# Main_board.net
KiCad netlist of a schematic drawn in Altium Designer
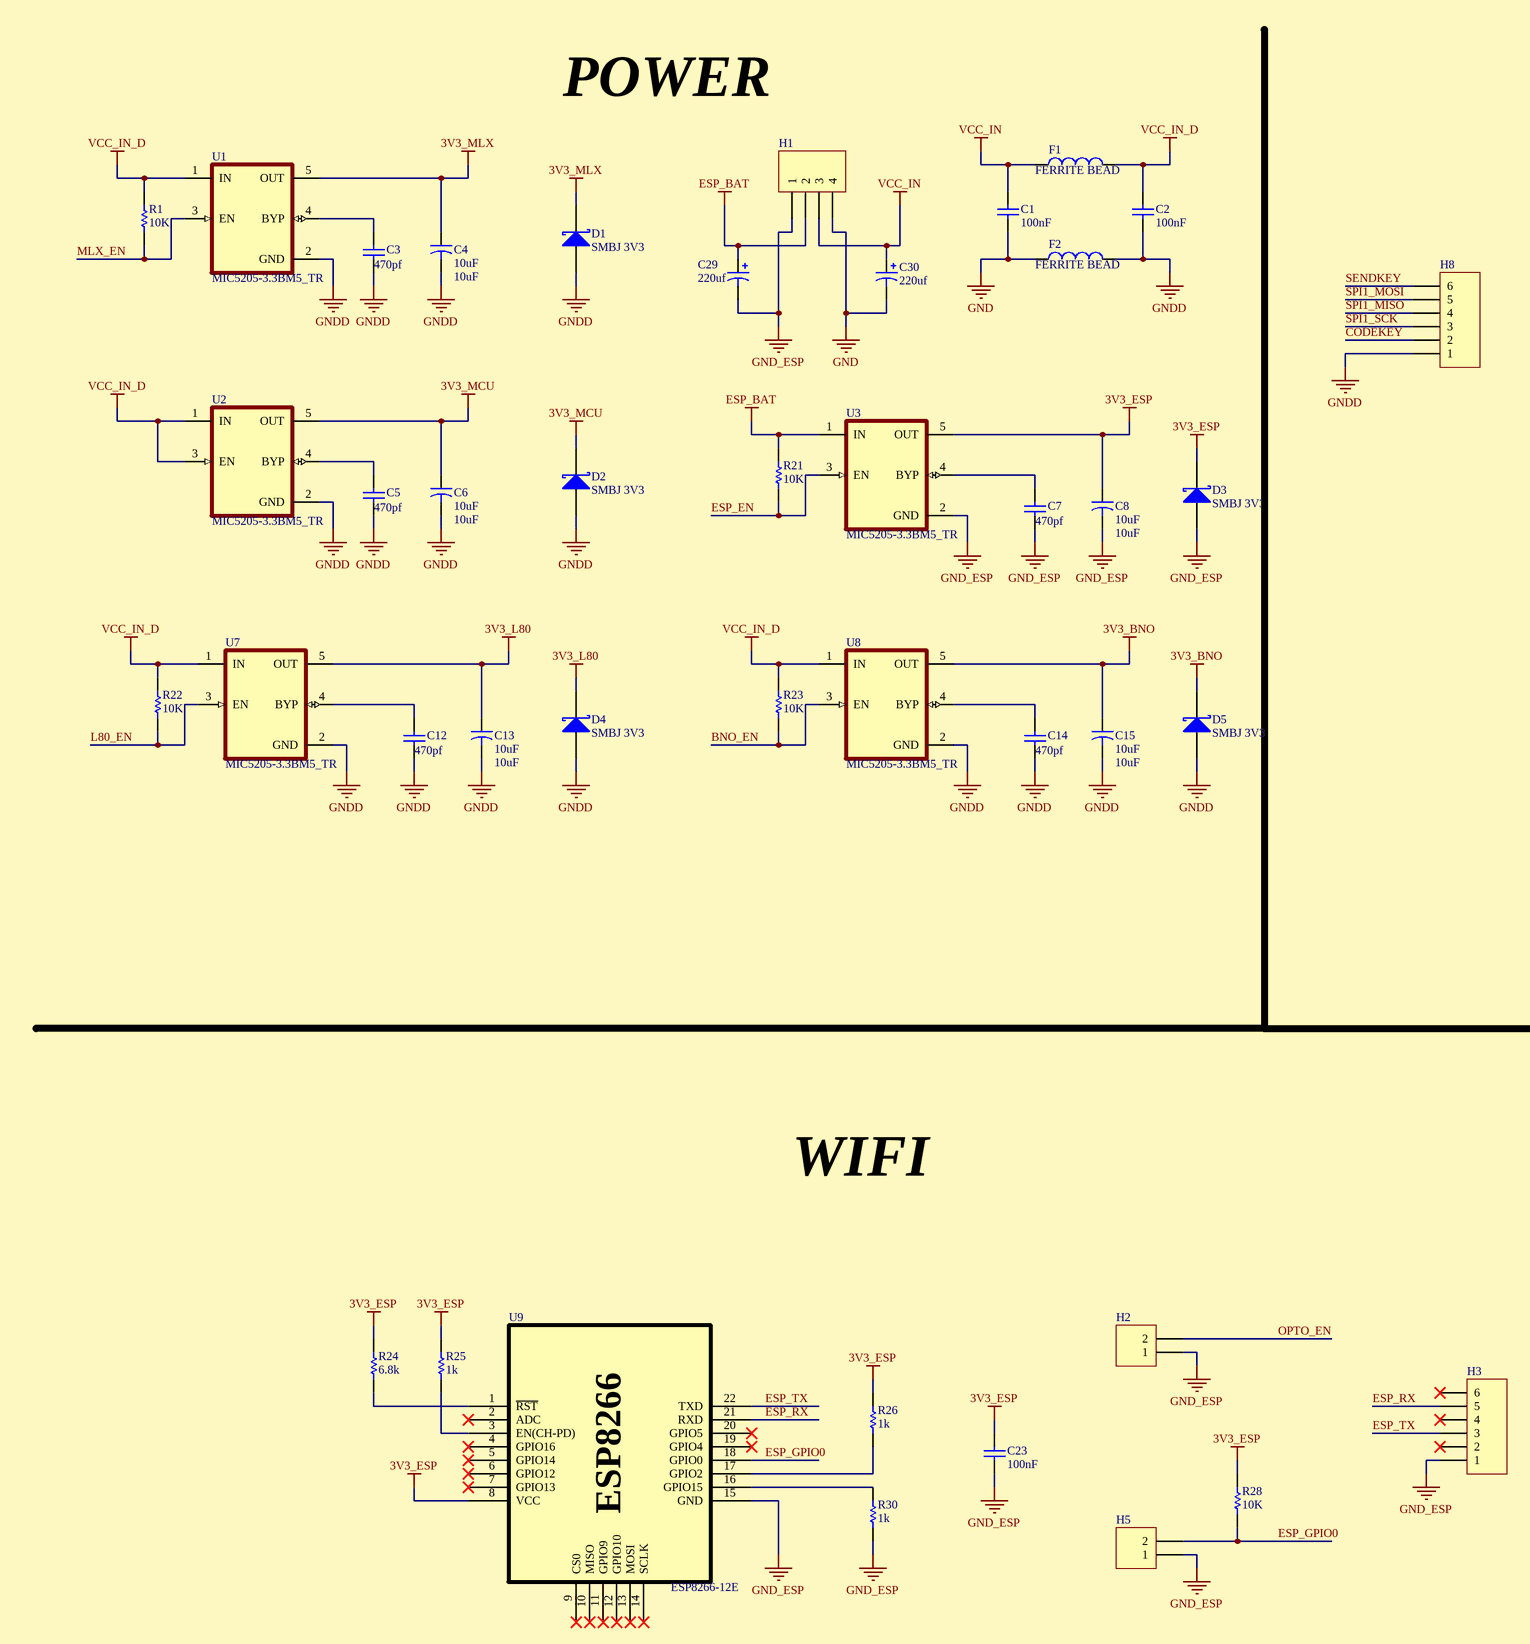
[diagram p0: Main_board.SchDoc, top left]
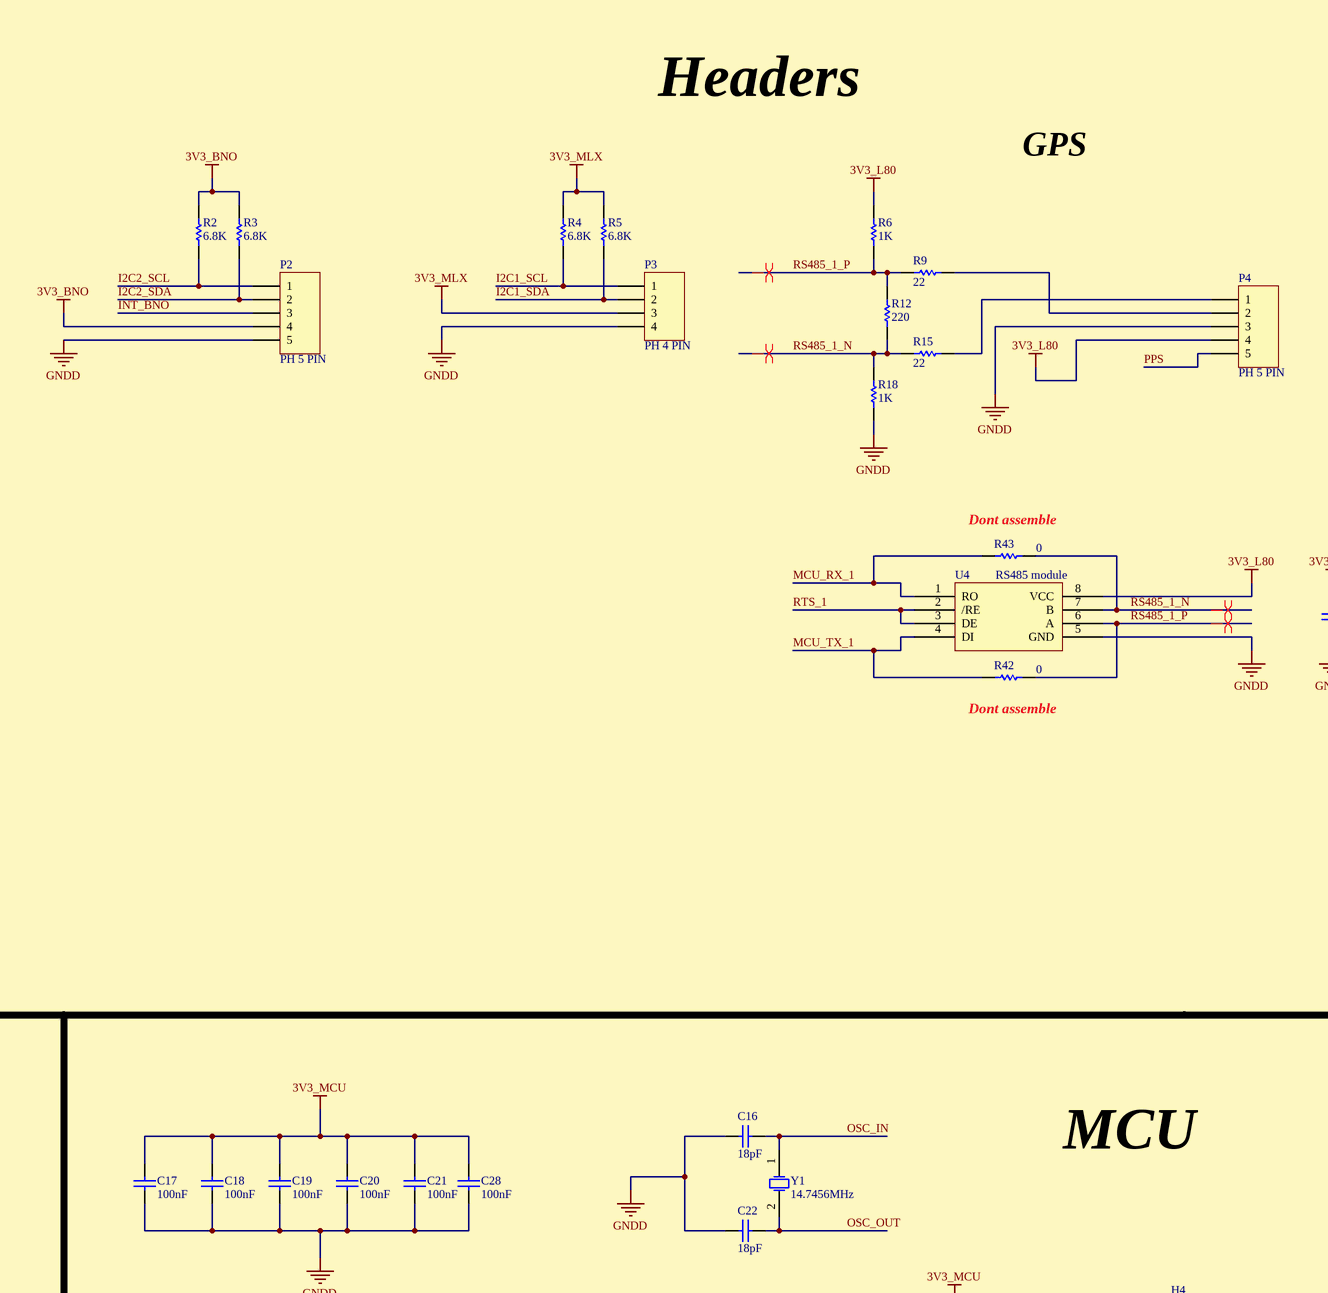
[diagram p1: Main_board.SchDoc, top middle]
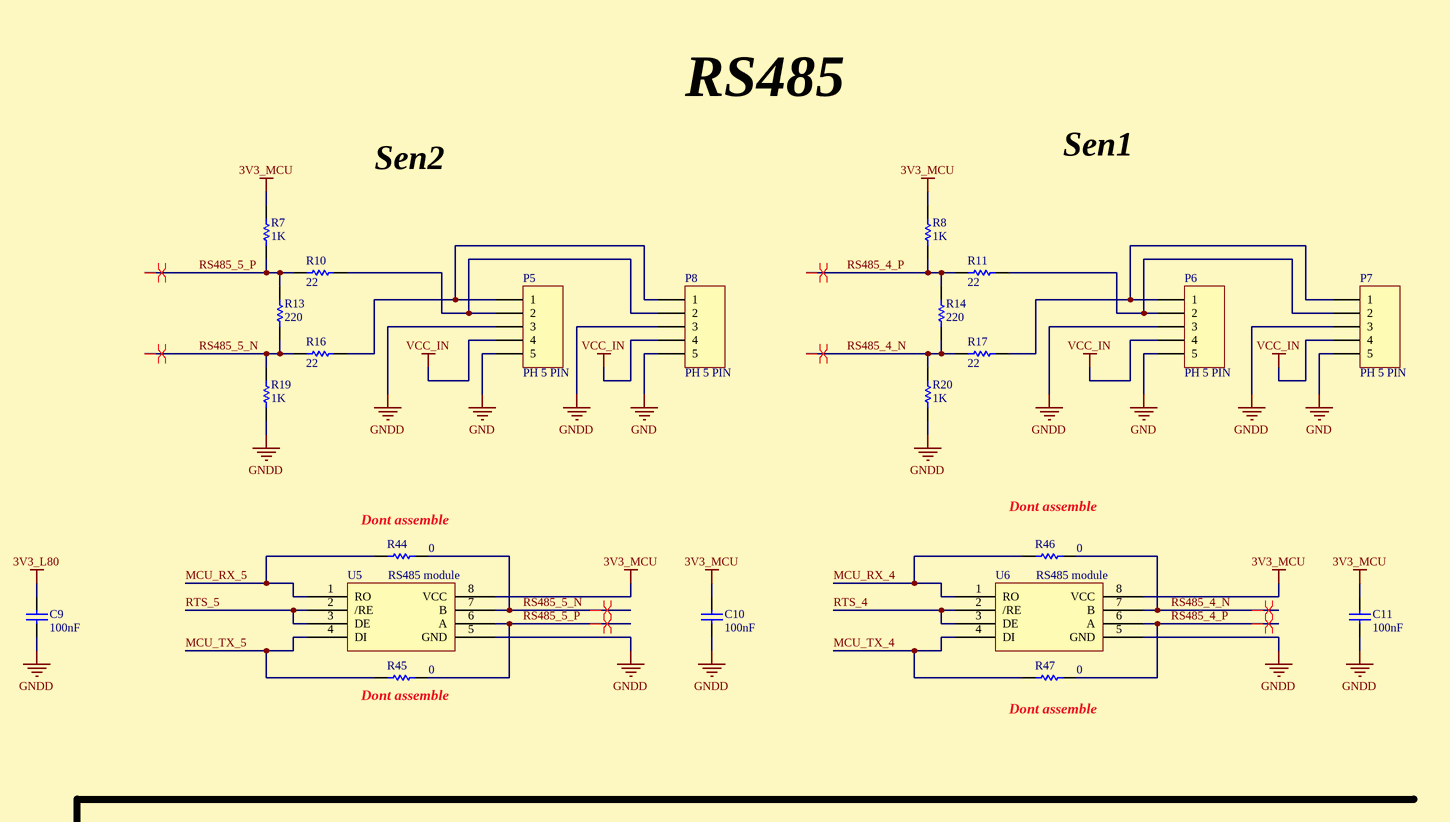
[diagram p2: Main_board.SchDoc, top right]
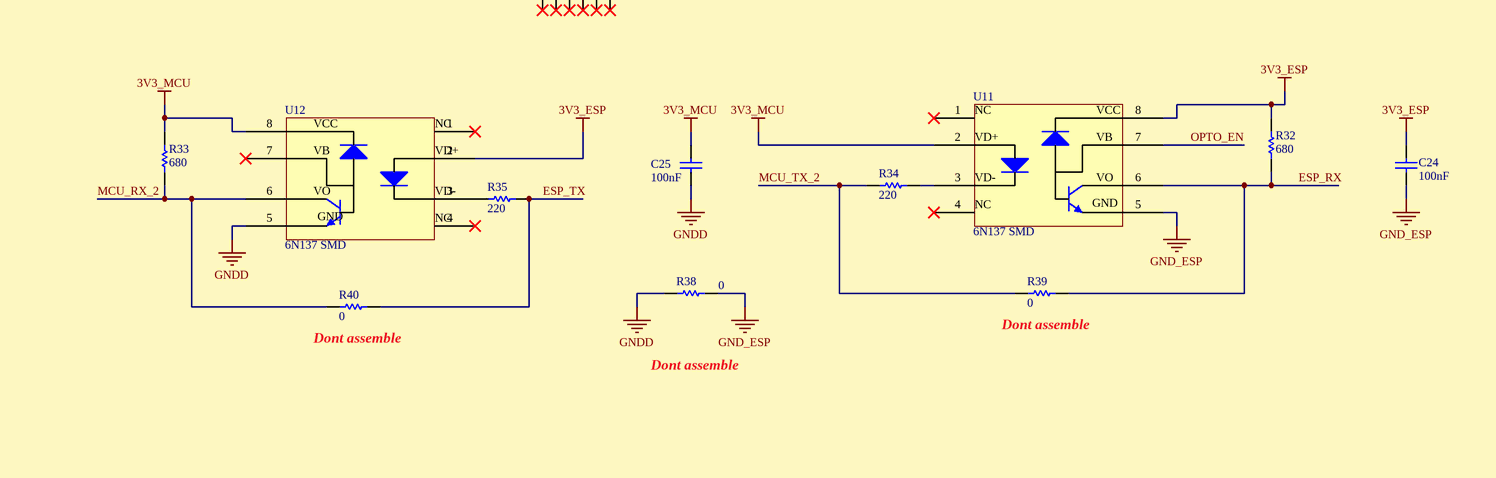
[diagram p3: Main_board.SchDoc, bottom left]
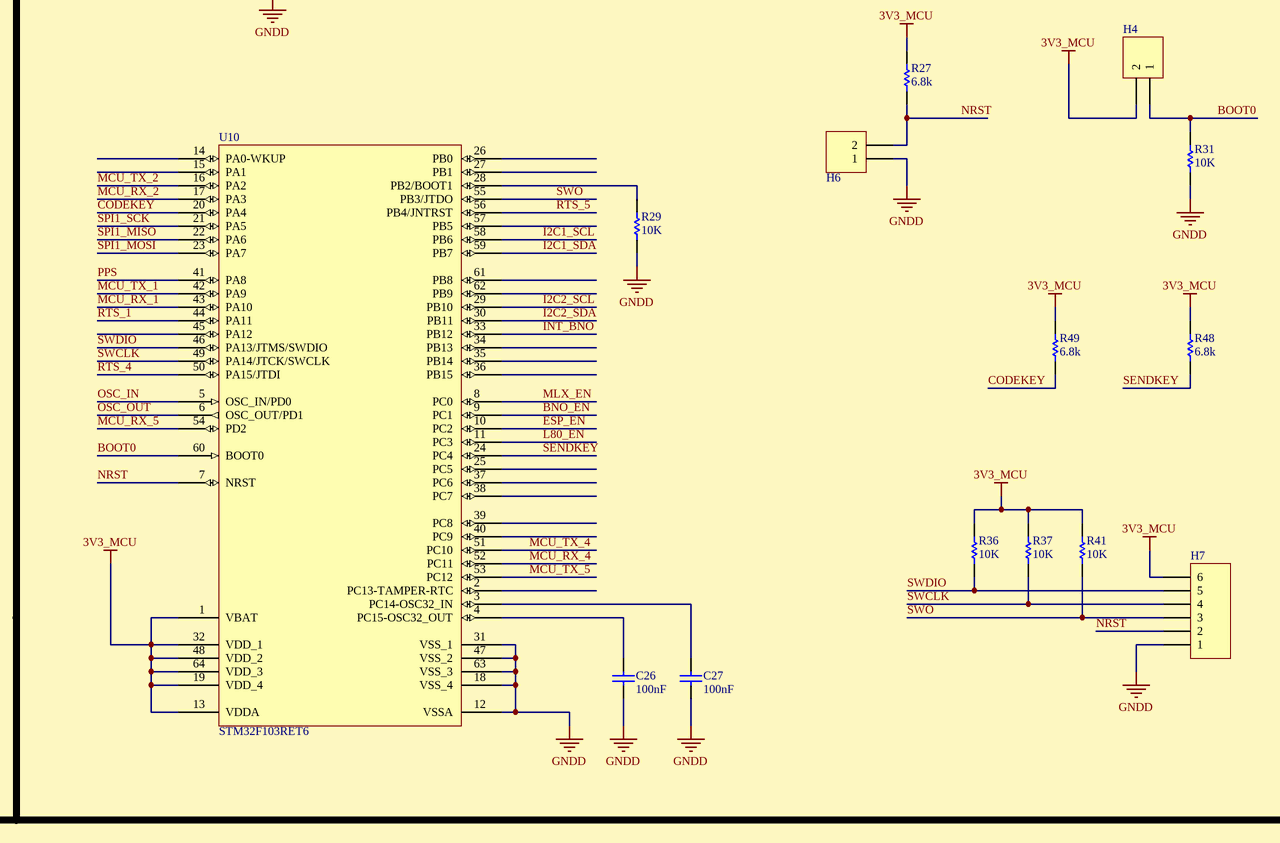
[diagram p4: Main_board.SchDoc, bottom middle]
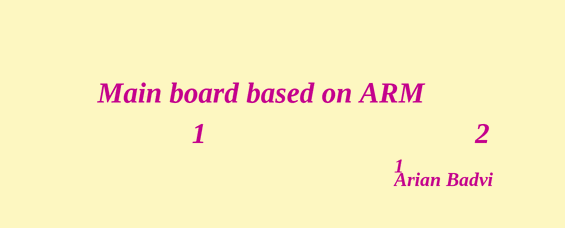
[diagram p5: Main_board.SchDoc, bottom right]

(export (version "E")
  (design (tool "Eeschema 10.0.6"))
  (components
    (comp (ref "C1")
      (value "100nF")
      (footprint "C0805")
      (description "Capacitor")
      (fields (field (name "PUBLISHER") "Altium Limited"))
      (libsource (lib "Miscellaneous Devices") (part "Cap"))
    )
    (comp (ref "C2")
      (value "100nF")
      (footprint "C0805")
      (description "Capacitor")
      (fields (field (name "PUBLISHER") "Altium Limited"))
      (libsource (lib "Miscellaneous Devices") (part "Cap"))
    )
    (comp (ref "C3")
      (value "470pf")
      (footprint "C0805")
      (description "Capacitor, 1206")
      (fields (field (name "PUBLISHER") "Altium Limited"))
      (libsource (lib "Library") (part "Cap"))
    )
    (comp (ref "C4")
      (value "10uF")
      (footprint "CAP_SMD_A")
      (description "Capacitor, 10uf")
      (fields (field (name "ALTIUM_VALUE") "10uF") (field (name "PUBLISHER") "Altium Limited"))
      (libsource (lib "Miscellaneous Devices") (part "Cap2"))
    )
    (comp (ref "C5")
      (value "470pf")
      (footprint "C0805")
      (description "Capacitor, 1206")
      (fields (field (name "PUBLISHER") "Altium Limited"))
      (libsource (lib "Library") (part "Cap"))
    )
    (comp (ref "C6")
      (value "10uF")
      (footprint "CAP_SMD_A")
      (description "Capacitor, 10uf")
      (fields (field (name "ALTIUM_VALUE") "10uF") (field (name "PUBLISHER") "Altium Limited"))
      (libsource (lib "Miscellaneous Devices") (part "Cap2"))
    )
    (comp (ref "C7")
      (value "470pf")
      (footprint "C0805")
      (description "Capacitor, 1206")
      (fields (field (name "PUBLISHER") "Altium Limited"))
      (libsource (lib "Library") (part "Cap"))
    )
    (comp (ref "C8")
      (value "10uF")
      (footprint "CAP_SMD_A")
      (description "Capacitor, 10uf")
      (fields (field (name "ALTIUM_VALUE") "10uF") (field (name "PUBLISHER") "Altium Limited"))
      (libsource (lib "Miscellaneous Devices") (part "Cap2"))
    )
    (comp (ref "C9")
      (value "100nF")
      (footprint "C0805")
      (description "Capacitor")
      (fields (field (name "PUBLISHER") "Altium Limited"))
      (libsource (lib "Miscellaneous Devices") (part "Cap"))
    )
    (comp (ref "C10")
      (value "100nF")
      (footprint "C0805")
      (description "Capacitor")
      (fields (field (name "PUBLISHER") "Altium Limited"))
      (libsource (lib "Miscellaneous Devices") (part "Cap"))
    )
    (comp (ref "C11")
      (value "100nF")
      (footprint "C0805")
      (description "Capacitor")
      (fields (field (name "PUBLISHER") "Altium Limited"))
      (libsource (lib "Miscellaneous Devices") (part "Cap"))
    )
    (comp (ref "C12")
      (value "470pf")
      (footprint "C0805")
      (description "Capacitor, 1206")
      (fields (field (name "PUBLISHER") "Altium Limited"))
      (libsource (lib "Library") (part "Cap"))
    )
    (comp (ref "C13")
      (value "10uF")
      (footprint "CAP_SMD_A")
      (description "Capacitor, 10uf")
      (fields (field (name "ALTIUM_VALUE") "10uF") (field (name "PUBLISHER") "Altium Limited"))
      (libsource (lib "Miscellaneous Devices") (part "Cap2"))
    )
    (comp (ref "C14")
      (value "470pf")
      (footprint "C0805")
      (description "Capacitor, 1206")
      (fields (field (name "PUBLISHER") "Altium Limited"))
      (libsource (lib "Library") (part "Cap"))
    )
    (comp (ref "C15")
      (value "10uF")
      (footprint "CAP_SMD_A")
      (description "Capacitor, 10uf")
      (fields (field (name "ALTIUM_VALUE") "10uF") (field (name "PUBLISHER") "Altium Limited"))
      (libsource (lib "Miscellaneous Devices") (part "Cap2"))
    )
    (comp (ref "C16")
      (value "18pF")
      (footprint "C0805")
      (description "Capacitor")
      (fields (field (name "PUBLISHER") "Altium Limited"))
      (libsource (lib "Miscellaneous Devices") (part "Cap"))
    )
    (comp (ref "C17")
      (value "100nF")
      (footprint "C0805")
      (description "Capacitor")
      (fields (field (name "PUBLISHER") "Altium Limited"))
      (libsource (lib "Miscellaneous Devices") (part "Cap"))
    )
    (comp (ref "C18")
      (value "100nF")
      (footprint "C0805")
      (description "Capacitor")
      (fields (field (name "PUBLISHER") "Altium Limited"))
      (libsource (lib "Miscellaneous Devices") (part "Cap"))
    )
    (comp (ref "C19")
      (value "100nF")
      (footprint "C0805")
      (description "Capacitor")
      (fields (field (name "PUBLISHER") "Altium Limited"))
      (libsource (lib "Miscellaneous Devices") (part "Cap"))
    )
    (comp (ref "C20")
      (value "100nF")
      (footprint "C0805")
      (description "Capacitor")
      (fields (field (name "PUBLISHER") "Altium Limited"))
      (libsource (lib "Miscellaneous Devices") (part "Cap"))
    )
    (comp (ref "C21")
      (value "100nF")
      (footprint "C0805")
      (description "Capacitor")
      (fields (field (name "PUBLISHER") "Altium Limited"))
      (libsource (lib "Miscellaneous Devices") (part "Cap"))
    )
    (comp (ref "C22")
      (value "18pF")
      (footprint "C0805")
      (description "Capacitor")
      (fields (field (name "PUBLISHER") "Altium Limited"))
      (libsource (lib "Miscellaneous Devices") (part "Cap"))
    )
    (comp (ref "C23")
      (value "100nF")
      (footprint "C0805")
      (description "Capacitor")
      (fields (field (name "PUBLISHER") "Altium Limited"))
      (libsource (lib "Miscellaneous Devices") (part "Cap"))
    )
    (comp (ref "C24")
      (value "100nF")
      (footprint "C0805")
      (description "Capacitor")
      (fields (field (name "PUBLISHER") "Altium Limited"))
      (libsource (lib "Miscellaneous Devices") (part "Cap"))
    )
    (comp (ref "C25")
      (value "100nF")
      (footprint "C0805")
      (description "Capacitor, 1206")
      (fields (field (name "PUBLISHER") "Altium Limited"))
      (libsource (lib "Miscellaneous Devices") (part "Cap"))
    )
    (comp (ref "C26")
      (value "100nF")
      (footprint "C0805")
      (description "Capacitor")
      (fields (field (name "PUBLISHER") "Altium Limited"))
      (libsource (lib "Miscellaneous Devices") (part "Cap"))
    )
    (comp (ref "C27")
      (value "100nF")
      (footprint "C0805")
      (description "Capacitor")
      (fields (field (name "PUBLISHER") "Altium Limited"))
      (libsource (lib "Miscellaneous Devices") (part "Cap"))
    )
    (comp (ref "C28")
      (value "100nF")
      (footprint "C0805")
      (description "Capacitor")
      (fields (field (name "PUBLISHER") "Altium Limited"))
      (libsource (lib "Miscellaneous Devices") (part "Cap"))
    )
    (comp (ref "C29")
      (value "220uf")
      (footprint "C_CYL_SMD2")
      (description "pol cap, Ele")
      (fields (field (name "PUBLISHER") "Altium Limited"))
      (libsource (lib "Library") (part "Cap Pol"))
    )
    (comp (ref "C30")
      (value "220uf")
      (footprint "C_CYL_SMD2")
      (description "pol cap, Ele")
      (fields (field (name "PUBLISHER") "Altium Limited"))
      (libsource (lib "Library") (part "Cap Pol"))
    )
    (comp (ref "D1")
      (value "SMBJ 3V3")
      (footprint "TVS")
      (description "TVS")
      (fields (field (name "PUBLISHER") "Altium Limited"))
      (libsource (lib "Miscellaneous Devices") (part "Diode 18TQ045"))
    )
    (comp (ref "D2")
      (value "SMBJ 3V3")
      (footprint "TVS")
      (description "TVS")
      (fields (field (name "PUBLISHER") "Altium Limited"))
      (libsource (lib "Miscellaneous Devices") (part "Diode 18TQ045"))
    )
    (comp (ref "D3")
      (value "SMBJ 3V3")
      (footprint "TVS")
      (description "TVS")
      (fields (field (name "PUBLISHER") "Altium Limited"))
      (libsource (lib "Miscellaneous Devices") (part "Diode 18TQ045"))
    )
    (comp (ref "D4")
      (value "SMBJ 3V3")
      (footprint "TVS")
      (description "TVS")
      (fields (field (name "PUBLISHER") "Altium Limited"))
      (libsource (lib "Miscellaneous Devices") (part "Diode 18TQ045"))
    )
    (comp (ref "D5")
      (value "SMBJ 3V3")
      (footprint "TVS")
      (description "TVS")
      (fields (field (name "PUBLISHER") "Altium Limited"))
      (libsource (lib "Miscellaneous Devices") (part "Diode 18TQ045"))
    )
    (comp (ref "F1")
      (value "FERRITE BEAD")
      (footprint "0805")
      (fields (field (name "PUBLISHER") "Altium Limited"))
      (libsource (lib "Miscellaneous Devices") (part "Inductor"))
    )
    (comp (ref "F2")
      (value "FERRITE BEAD")
      (footprint "0805")
      (fields (field (name "PUBLISHER") "Altium Limited"))
      (libsource (lib "Miscellaneous Devices") (part "Inductor"))
    )
    (comp (ref "H1")
      (value "XH 4pin")
      (footprint "XH_4")
      (description "White Connector 4pin")
      (fields (field (name "PUBLISHER") "Altium Limited"))
      (libsource (lib "Miscellaneous Connectors") (part "Header 4"))
    )
    (comp (ref "H2")
      (value "Pin Header, 1.27")
      (footprint "H_1.27")
      (description "Header, 2-Pin, 1.27mm")
      (fields (field (name "PUBLISHER") "Altium Limited"))
      (libsource (lib "Miscellaneous Connectors") (part "Header 2"))
    )
    (comp (ref "H3")
      (value "PB 6pin SMD")
      (footprint "PB_6_SMD")
      (description "White SMD Connector 6pin")
      (fields (field (name "PUBLISHER") "Altium Limited"))
      (libsource (lib "Miscellaneous Connectors") (part "Header 6"))
    )
    (comp (ref "H4")
      (value "Pin Header, 1.27")
      (footprint "H_1.27")
      (description "Header, 2-Pin, 1.27mm")
      (fields (field (name "PUBLISHER") "Altium Limited"))
      (libsource (lib "") (part "Header 2_1"))
    )
    (comp (ref "H5")
      (value "Pin Header, 1.27")
      (footprint "H_1.27")
      (description "Header, 2-Pin, 1.27mm")
      (fields (field (name "PUBLISHER") "Altium Limited"))
      (libsource (lib "Miscellaneous Connectors") (part "Header 2"))
    )
    (comp (ref "H6")
      (value "Pin Header, 1.27")
      (footprint "H_1.27")
      (description "Header, 2-Pin, 1.27mm")
      (fields (field (name "PUBLISHER") "Altium Limited"))
      (libsource (lib "Miscellaneous Connectors") (part "Header 2"))
    )
    (comp (ref "H7")
      (value "PB 6pin SMD")
      (footprint "PB_6_SMD")
      (description "White SMD Connector 6pin")
      (fields (field (name "PUBLISHER") "Altium Limited"))
      (libsource (lib "Miscellaneous Connectors") (part "Header 6"))
    )
    (comp (ref "H8")
      (value "PB 6pin SMD")
      (footprint "PB_6_SMD")
      (description "White SMD Connector 6pin")
      (fields (field (name "PUBLISHER") "Altium Limited"))
      (libsource (lib "Miscellaneous Connectors") (part "Header 6"))
    )
    (comp (ref "P2")
      (value "PH 5 PIN")
      (footprint "PH_5")
      (description "Header, 5-Pin")
      (fields (field (name "PUBLISHER") "Altium Limited"))
      (libsource (lib "Miscellaneous Connectors") (part "Header 5"))
    )
    (comp (ref "P3")
      (value "PH 4 PIN")
      (footprint "PH_4")
      (description "Header, 4-Pin")
      (fields (field (name "PUBLISHER") "Altium Limited"))
      (libsource (lib "") (part "Header 4_1"))
    )
    (comp (ref "P4")
      (value "PH 5 PIN")
      (footprint "PH_5")
      (description "Header, 5-Pin")
      (fields (field (name "PUBLISHER") "Altium Limited"))
      (libsource (lib "Miscellaneous Connectors") (part "Header 5"))
    )
    (comp (ref "P5")
      (value "PH 5 PIN")
      (footprint "PH_5")
      (description "Header, 5-Pin")
      (fields (field (name "PUBLISHER") "Altium Limited"))
      (libsource (lib "Miscellaneous Connectors") (part "Header 5"))
    )
    (comp (ref "P6")
      (value "PH 5 PIN")
      (footprint "PH_5")
      (description "Header, 5-Pin")
      (fields (field (name "PUBLISHER") "Altium Limited"))
      (libsource (lib "Miscellaneous Connectors") (part "Header 5"))
    )
    (comp (ref "P7")
      (value "PH 5 PIN")
      (footprint "PH_5")
      (description "Header, 5-Pin")
      (fields (field (name "PUBLISHER") "Altium Limited"))
      (libsource (lib "Miscellaneous Connectors") (part "Header 5"))
    )
    (comp (ref "P8")
      (value "PH 5 PIN")
      (footprint "PH_5")
      (description "Header, 5-Pin")
      (fields (field (name "PUBLISHER") "Altium Limited"))
      (libsource (lib "Miscellaneous Connectors") (part "Header 5"))
    )
    (comp (ref "R1")
      (value "10K")
      (footprint "0805")
      (description "General Resistor")
      (fields (field (name "PUBLISHER") "Altium Limited"))
      (libsource (lib "Library") (part "Resistor"))
    )
    (comp (ref "R2")
      (value "6.8K")
      (footprint "0805")
      (description "Resistor")
      (fields (field (name "PUBLISHER") "Altium Limited"))
      (libsource (lib "Miscellaneous Devices") (part "Res1"))
    )
    (comp (ref "R3")
      (value "6.8K")
      (footprint "0805")
      (description "Resistor")
      (fields (field (name "PUBLISHER") "Altium Limited"))
      (libsource (lib "Miscellaneous Devices") (part "Res1"))
    )
    (comp (ref "R4")
      (value "6.8K")
      (footprint "0805")
      (description "Resistor")
      (fields (field (name "PUBLISHER") "Altium Limited"))
      (libsource (lib "Miscellaneous Devices") (part "Res1"))
    )
    (comp (ref "R5")
      (value "6.8K")
      (footprint "0805")
      (description "Resistor")
      (fields (field (name "PUBLISHER") "Altium Limited"))
      (libsource (lib "Miscellaneous Devices") (part "Res1"))
    )
    (comp (ref "R6")
      (value "1K")
      (footprint "0805")
      (description "Resistor")
      (fields (field (name "PUBLISHER") "Altium Limited"))
      (libsource (lib "Miscellaneous Devices") (part "Res1"))
    )
    (comp (ref "R7")
      (value "1K")
      (footprint "0805")
      (description "Resistor")
      (fields (field (name "PUBLISHER") "Altium Limited"))
      (libsource (lib "Miscellaneous Devices") (part "Res1"))
    )
    (comp (ref "R8")
      (value "1K")
      (footprint "0805")
      (description "Resistor")
      (fields (field (name "PUBLISHER") "Altium Limited"))
      (libsource (lib "Miscellaneous Devices") (part "Res1"))
    )
    (comp (ref "R9")
      (value "22")
      (footprint "0805")
      (description "Resistor")
      (fields (field (name "PUBLISHER") "Altium Limited"))
      (libsource (lib "Miscellaneous Devices") (part "Res1"))
    )
    (comp (ref "R10")
      (value "22")
      (footprint "0805")
      (description "Resistor")
      (fields (field (name "PUBLISHER") "Altium Limited"))
      (libsource (lib "Miscellaneous Devices") (part "Res1"))
    )
    (comp (ref "R11")
      (value "22")
      (footprint "0805")
      (description "Resistor")
      (fields (field (name "PUBLISHER") "Altium Limited"))
      (libsource (lib "Miscellaneous Devices") (part "Res1"))
    )
    (comp (ref "R12")
      (value "220")
      (footprint "0805")
      (description "Resistor")
      (fields (field (name "PUBLISHER") "Altium Limited"))
      (libsource (lib "Miscellaneous Devices") (part "Res1"))
    )
    (comp (ref "R13")
      (value "220")
      (footprint "0805")
      (description "Resistor")
      (fields (field (name "PUBLISHER") "Altium Limited"))
      (libsource (lib "Miscellaneous Devices") (part "Res1"))
    )
    (comp (ref "R14")
      (value "220")
      (footprint "0805")
      (description "Resistor")
      (fields (field (name "PUBLISHER") "Altium Limited"))
      (libsource (lib "Miscellaneous Devices") (part "Res1"))
    )
    (comp (ref "R15")
      (value "22")
      (footprint "0805")
      (description "Resistor")
      (fields (field (name "PUBLISHER") "Altium Limited"))
      (libsource (lib "Miscellaneous Devices") (part "Res1"))
    )
    (comp (ref "R16")
      (value "22")
      (footprint "0805")
      (description "Resistor")
      (fields (field (name "PUBLISHER") "Altium Limited"))
      (libsource (lib "Miscellaneous Devices") (part "Res1"))
    )
    (comp (ref "R17")
      (value "22")
      (footprint "0805")
      (description "Resistor")
      (fields (field (name "PUBLISHER") "Altium Limited"))
      (libsource (lib "Miscellaneous Devices") (part "Res1"))
    )
    (comp (ref "R18")
      (value "1K")
      (footprint "0805")
      (description "Resistor")
      (fields (field (name "PUBLISHER") "Altium Limited"))
      (libsource (lib "Miscellaneous Devices") (part "Res1"))
    )
    (comp (ref "R19")
      (value "1K")
      (footprint "0805")
      (description "Resistor")
      (fields (field (name "PUBLISHER") "Altium Limited"))
      (libsource (lib "Miscellaneous Devices") (part "Res1"))
    )
    (comp (ref "R20")
      (value "1K")
      (footprint "0805")
      (description "Resistor")
      (fields (field (name "PUBLISHER") "Altium Limited"))
      (libsource (lib "Miscellaneous Devices") (part "Res1"))
    )
    (comp (ref "R21")
      (value "10K")
      (footprint "0805")
      (description "General Resistor")
      (fields (field (name "PUBLISHER") "Altium Limited"))
      (libsource (lib "Library") (part "Resistor"))
    )
    (comp (ref "R22")
      (value "10K")
      (footprint "0805")
      (description "General Resistor")
      (fields (field (name "PUBLISHER") "Altium Limited"))
      (libsource (lib "Library") (part "Resistor"))
    )
    (comp (ref "R23")
      (value "10K")
      (footprint "0805")
      (description "General Resistor")
      (fields (field (name "PUBLISHER") "Altium Limited"))
      (libsource (lib "Library") (part "Resistor"))
    )
    (comp (ref "R24")
      (value "6.8k")
      (footprint "0805")
      (description "Resistor, 6.8k")
      (fields (field (name "PUBLISHER") "Altium Limited"))
      (libsource (lib "Miscellaneous Devices") (part "Res1"))
    )
    (comp (ref "R25")
      (value "1k")
      (footprint "0805")
      (description "Resistor")
      (fields (field (name "PUBLISHER") "Altium Limited"))
      (libsource (lib "Miscellaneous Devices") (part "Res1"))
    )
    (comp (ref "R26")
      (value "1k")
      (footprint "0805")
      (description "Resistor")
      (fields (field (name "PUBLISHER") "Altium Limited"))
      (libsource (lib "Miscellaneous Devices") (part "Res1"))
    )
    (comp (ref "R27")
      (value "6.8k")
      (footprint "0805")
      (description "Resistor, 6.8k")
      (fields (field (name "PUBLISHER") "Altium Limited"))
      (libsource (lib "Miscellaneous Devices") (part "Res1"))
    )
    (comp (ref "R28")
      (value "10K")
      (footprint "0805")
      (description "Resistor")
      (fields (field (name "PUBLISHER") "Altium Limited"))
      (libsource (lib "Miscellaneous Devices") (part "Res1"))
    )
    (comp (ref "R29")
      (value "10K")
      (footprint "0805")
      (description "Resistor, 10k")
      (fields (field (name "PUBLISHER") "Altium Limited"))
      (libsource (lib "Miscellaneous Devices") (part "Res1"))
    )
    (comp (ref "R30")
      (value "1k")
      (footprint "0805")
      (description "Resistor")
      (fields (field (name "PUBLISHER") "Altium Limited"))
      (libsource (lib "Miscellaneous Devices") (part "Res1"))
    )
    (comp (ref "R31")
      (value "10K")
      (footprint "0805")
      (description "Resistor, 10k")
      (fields (field (name "PUBLISHER") "Altium Limited"))
      (libsource (lib "Miscellaneous Devices") (part "Res1"))
    )
    (comp (ref "R32")
      (value "680")
      (footprint "0805")
      (description "General Resistor")
      (fields (field (name "PUBLISHER") "Altium Limited"))
      (libsource (lib "Library") (part "Resistor"))
    )
    (comp (ref "R33")
      (value "680")
      (footprint "0805")
      (description "Resistor, 6.8k")
      (fields (field (name "PUBLISHER") "Altium Limited"))
      (libsource (lib "Miscellaneous Devices") (part "Res1"))
    )
    (comp (ref "R34")
      (value "220")
      (footprint "0805")
      (description "General Resistor")
      (fields (field (name "PUBLISHER") "Altium Limited"))
      (libsource (lib "Library") (part "Resistor"))
    )
    (comp (ref "R35")
      (value "220")
      (footprint "0805")
      (description "General Resistor")
      (fields (field (name "PUBLISHER") "Altium Limited"))
      (libsource (lib "Library") (part "Resistor"))
    )
    (comp (ref "R36")
      (value "10K")
      (footprint "0805")
      (description "Resistor, 10K")
      (fields (field (name "PUBLISHER") "Altium Limited"))
      (libsource (lib "Miscellaneous Devices") (part "Res1"))
    )
    (comp (ref "R37")
      (value "10K")
      (footprint "0805")
      (description "Resistor, 10K")
      (fields (field (name "PUBLISHER") "Altium Limited"))
      (libsource (lib "Miscellaneous Devices") (part "Res1"))
    )
    (comp (ref "R38")
      (value "0")
      (footprint "0603")
      (description "General Resistor")
      (fields (field (name "PUBLISHER") "Altium Limited"))
      (libsource (lib "Library") (part "Resistor"))
    )
    (comp (ref "R39")
      (value "0")
      (footprint "0603")
      (description "General Resistor")
      (fields (field (name "PUBLISHER") "Altium Limited"))
      (libsource (lib "Library") (part "Resistor"))
    )
    (comp (ref "R40")
      (value "0")
      (footprint "0603")
      (description "General Resistor")
      (fields (field (name "PUBLISHER") "Altium Limited"))
      (libsource (lib "Library") (part "Resistor"))
    )
    (comp (ref "R41")
      (value "10K")
      (footprint "0805")
      (description "Resistor, 10K")
      (fields (field (name "PUBLISHER") "Altium Limited"))
      (libsource (lib "Miscellaneous Devices") (part "Res1"))
    )
    (comp (ref "R42")
      (value "0")
      (footprint "0603")
      (description "Resistor, 10K")
      (fields (field (name "PUBLISHER") "Altium Limited"))
      (libsource (lib "Miscellaneous Devices") (part "Res1"))
    )
    (comp (ref "R43")
      (value "0")
      (footprint "0603")
      (description "Resistor, 10K")
      (fields (field (name "PUBLISHER") "Altium Limited"))
      (libsource (lib "Miscellaneous Devices") (part "Res1"))
    )
    (comp (ref "R44")
      (value "0")
      (footprint "0603")
      (description "Resistor, 10K")
      (fields (field (name "PUBLISHER") "Altium Limited"))
      (libsource (lib "Miscellaneous Devices") (part "Res1"))
    )
    (comp (ref "R45")
      (value "0")
      (footprint "0603")
      (description "Resistor, 10K")
      (fields (field (name "PUBLISHER") "Altium Limited"))
      (libsource (lib "Miscellaneous Devices") (part "Res1"))
    )
    (comp (ref "R46")
      (value "0")
      (footprint "0603")
      (description "Resistor, 10K")
      (fields (field (name "PUBLISHER") "Altium Limited"))
      (libsource (lib "Miscellaneous Devices") (part "Res1"))
    )
    (comp (ref "R47")
      (value "0")
      (footprint "0603")
      (description "Resistor, 10K")
      (fields (field (name "PUBLISHER") "Altium Limited"))
      (libsource (lib "Miscellaneous Devices") (part "Res1"))
    )
    (comp (ref "R48")
      (value "6.8k")
      (footprint "0805")
      (description "Resistor, 6.8k")
      (fields (field (name "PUBLISHER") "Altium Limited"))
      (libsource (lib "Miscellaneous Devices") (part "Res1"))
    )
    (comp (ref "R49")
      (value "6.8k")
      (footprint "0805")
      (description "Resistor, 6.8k")
      (fields (field (name "PUBLISHER") "Altium Limited"))
      (libsource (lib "Miscellaneous Devices") (part "Res1"))
    )
    (comp (ref "U1")
      (value "MIC5205-3.3BM5_TR")
      (footprint "SOT23_5")
      (description "Linear Voltage Regulator IC 1 Output 150mA SOT-23-5")
      (fields (field (name "MP") "MIC5205-3.3BM5 TR") (field (name "MF") "Micrel"))
      (libsource (lib "Main_board") (part "MIC5205-3.3BM5_TR"))
    )
    (comp (ref "U2")
      (value "MIC5205-3.3BM5_TR")
      (footprint "SOT23_5")
      (description "Linear Voltage Regulator IC 1 Output 150mA SOT-23-5")
      (fields (field (name "MP") "MIC5205-3.3BM5 TR") (field (name "MF") "Micrel"))
      (libsource (lib "Main_board") (part "MIC5205-3.3BM5_TR"))
    )
    (comp (ref "U3")
      (value "MIC5205-3.3BM5_TR")
      (footprint "SOT23_5")
      (description "Linear Voltage Regulator IC 1 Output 150mA SOT-23-5")
      (fields (field (name "MP") "MIC5205-3.3BM5 TR") (field (name "MF") "Micrel"))
      (libsource (lib "Main_board") (part "MIC5205-3.3BM5_TR"))
    )
    (comp (ref "U4")
      (value "RS485 module")
      (footprint "SOP8")
      (libsource (lib "Schlib_RS485") (part "rs485"))
    )
    (comp (ref "U5")
      (value "RS485 module")
      (footprint "SOP8")
      (libsource (lib "Schlib_RS485") (part "rs485"))
    )
    (comp (ref "U6")
      (value "RS485 module")
      (footprint "SOP8")
      (libsource (lib "Schlib_RS485") (part "rs485"))
    )
    (comp (ref "U7")
      (value "MIC5205-3.3BM5_TR")
      (footprint "SOT23_5")
      (description "Linear Voltage Regulator IC 1 Output 150mA SOT-23-5")
      (fields (field (name "MP") "MIC5205-3.3BM5 TR") (field (name "MF") "Micrel"))
      (libsource (lib "Main_board") (part "MIC5205-3.3BM5_TR"))
    )
    (comp (ref "U8")
      (value "MIC5205-3.3BM5_TR")
      (footprint "SOT23_5")
      (description "Linear Voltage Regulator IC 1 Output 150mA SOT-23-5")
      (fields (field (name "MP") "MIC5205-3.3BM5 TR") (field (name "MF") "Micrel"))
      (libsource (lib "Main_board") (part "MIC5205-3.3BM5_TR"))
    )
    (comp (ref "U9")
      (value "ESP8266-12E")
      (footprint "ESP8266_ESP12E")
      (libsource (lib "ESP8266") (part "ESP8266"))
    )
    (comp (ref "U10")
      (value "STM32F103RET6")
      (footprint "LQFP64")
      (description "STM32 ARM-based 32-bit MCU with 64 Kbytes Flash, 64-pin LQFP, Industrial Temperature")
      (fields (field (name "PUBLISHER") "Altium Limited"))
      (libsource (lib "ST Microcontroller 32-Bit STM32") (part "STM32F103R8T6"))
    )
    (comp (ref "U11") (value "6N137 SMD") (footprint "DIP_8SMD") (libsource (lib "Library") (part "6N137")))
    (comp (ref "U12") (value "6N137 SMD") (footprint "DIP_8SMD") (libsource (lib "") (part "6N137_1")))
    (comp (ref "Y1")
      (value "14.7456MHz")
      (footprint "XTAL_SMD")
      (description "Crystal Oscillator, 14.7456KHz")
      (fields (field (name "PUBLISHER") "Altium Limited"))
      (libsource (lib "Miscellaneous Devices") (part "XTAL"))
    )
  )
  (nets
    (net (code "1") (name "/BNO_EN") (class "Default")
      (node (ref "R23") (pin "2") (pinfunction "2_2") (pintype "passive"))
      (node (ref "U10") (pin "9") (pinfunction "PC1_9") (pintype "bidirectional"))
      (node (ref "U8") (pin "3") (pinfunction "EN_3") (pintype "input"))
    )
    (net (code "2") (name "/BOOT0") (class "Default")
      (node (ref "H4") (pin "1") (pinfunction "1_1") (pintype "passive"))
      (node (ref "R31") (pin "1") (pinfunction "1_1") (pintype "passive"))
      (node (ref "U10") (pin "60") (pinfunction "BOOT0_60") (pintype "input"))
    )
    (net (code "3") (name "/CODEKEY") (class "Default")
      (node (ref "H8") (pin "2") (pinfunction "2_2") (pintype "passive"))
      (node (ref "R49") (pin "2") (pinfunction "2_2") (pintype "passive"))
      (node (ref "U10") (pin "20") (pinfunction "PA4_20") (pintype "bidirectional"))
    )
    (net (code "4") (name "/ESP_EN") (class "Default")
      (node (ref "R21") (pin "2") (pinfunction "2_2") (pintype "passive"))
      (node (ref "U10") (pin "10") (pinfunction "PC2_10") (pintype "bidirectional"))
      (node (ref "U3") (pin "3") (pinfunction "EN_3") (pintype "input"))
    )
    (net (code "5") (name "/ESP_GPIO0") (class "Default")
      (node (ref "H5") (pin "2") (pinfunction "2_2") (pintype "passive"))
      (node (ref "R28") (pin "1") (pinfunction "1_1") (pintype "passive"))
      (node (ref "U9") (pin "18") (pinfunction "GPIO0_18") (pintype "passive"))
    )
    (net (code "6") (name "/ESP_RX") (class "Default")
      (node (ref "H3") (pin "5") (pinfunction "5_5") (pintype "passive"))
      (node (ref "R32") (pin "1") (pinfunction "1_1") (pintype "passive"))
      (node (ref "R39") (pin "2") (pinfunction "2_2") (pintype "passive"))
      (node (ref "U11") (pin "6") (pinfunction "6_6") (pintype "passive"))
      (node (ref "U9") (pin "21") (pinfunction "RXD_21") (pintype "passive"))
    )
    (net (code "7") (name "/ESP_TX") (class "Default")
      (node (ref "H3") (pin "3") (pinfunction "3_3") (pintype "passive"))
      (node (ref "R35") (pin "2") (pinfunction "2_2") (pintype "passive"))
      (node (ref "R40") (pin "2") (pinfunction "2_2") (pintype "passive"))
      (node (ref "U9") (pin "22") (pinfunction "TXD_22") (pintype "passive"))
    )
    (net (code "8") (name "/I2C1_SCL") (class "Default")
      (node (ref "P3") (pin "1") (pinfunction "1_1") (pintype "passive"))
      (node (ref "R4") (pin "1") (pinfunction "1_1") (pintype "passive"))
      (node (ref "U10") (pin "58") (pinfunction "PB6_58") (pintype "bidirectional"))
    )
    (net (code "9") (name "/I2C1_SDA") (class "Default")
      (node (ref "P3") (pin "2") (pinfunction "2_2") (pintype "passive"))
      (node (ref "R5") (pin "1") (pinfunction "1_1") (pintype "passive"))
      (node (ref "U10") (pin "59") (pinfunction "PB7_59") (pintype "bidirectional"))
    )
    (net (code "10") (name "/I2C2_SCL") (class "Default")
      (node (ref "P2") (pin "1") (pinfunction "1_1") (pintype "passive"))
      (node (ref "R2") (pin "1") (pinfunction "1_1") (pintype "passive"))
      (node (ref "U10") (pin "29") (pinfunction "PB10_29") (pintype "bidirectional"))
    )
    (net (code "11") (name "/I2C2_SDA") (class "Default")
      (node (ref "P2") (pin "2") (pinfunction "2_2") (pintype "passive"))
      (node (ref "R3") (pin "1") (pinfunction "1_1") (pintype "passive"))
      (node (ref "U10") (pin "30") (pinfunction "PB11_30") (pintype "bidirectional"))
    )
    (net (code "12") (name "/INT_BNO") (class "Default")
      (node (ref "P2") (pin "3") (pinfunction "3_3") (pintype "passive"))
      (node (ref "U10") (pin "33") (pinfunction "PB12_33") (pintype "bidirectional"))
    )
    (net (code "13") (name "/L80_EN") (class "Default")
      (node (ref "R22") (pin "2") (pinfunction "2_2") (pintype "passive"))
      (node (ref "U10") (pin "11") (pinfunction "PC3_11") (pintype "bidirectional"))
      (node (ref "U7") (pin "3") (pinfunction "EN_3") (pintype "input"))
    )
    (net (code "14") (name "/MCU_RX_1") (class "Default")
      (node (ref "R43") (pin "1") (pinfunction "1_1") (pintype "passive"))
      (node (ref "U10") (pin "43") (pinfunction "PA10_43") (pintype "bidirectional"))
      (node (ref "U4") (pin "1") (pinfunction "RO_1") (pintype "passive"))
    )
    (net (code "15") (name "/MCU_RX_2") (class "Default")
      (node (ref "R33") (pin "2") (pinfunction "2_2") (pintype "passive"))
      (node (ref "R40") (pin "1") (pinfunction "1_1") (pintype "passive"))
      (node (ref "U10") (pin "17") (pinfunction "PA3_17") (pintype "bidirectional"))
      (node (ref "U12") (pin "6") (pinfunction "6_6") (pintype "passive"))
    )
    (net (code "16") (name "/MCU_RX_4") (class "Default")
      (node (ref "R46") (pin "1") (pinfunction "1_1") (pintype "passive"))
      (node (ref "U10") (pin "52") (pinfunction "PC11_52") (pintype "bidirectional"))
      (node (ref "U6") (pin "1") (pinfunction "RO_1") (pintype "passive"))
    )
    (net (code "17") (name "/MCU_RX_5") (class "Default")
      (node (ref "R44") (pin "1") (pinfunction "1_1") (pintype "passive"))
      (node (ref "U10") (pin "54") (pinfunction "PD2_54") (pintype "bidirectional"))
      (node (ref "U5") (pin "1") (pinfunction "RO_1") (pintype "passive"))
    )
    (net (code "18") (name "/MCU_TX_1") (class "Default")
      (node (ref "R42") (pin "1") (pinfunction "1_1") (pintype "passive"))
      (node (ref "U10") (pin "42") (pinfunction "PA9_42") (pintype "bidirectional"))
      (node (ref "U4") (pin "4") (pinfunction "DI_4") (pintype "passive"))
    )
    (net (code "19") (name "/MCU_TX_2") (class "Default")
      (node (ref "R34") (pin "1") (pinfunction "1_1") (pintype "passive"))
      (node (ref "R39") (pin "1") (pinfunction "1_1") (pintype "passive"))
      (node (ref "U10") (pin "16") (pinfunction "PA2_16") (pintype "bidirectional"))
    )
    (net (code "20") (name "/MCU_TX_4") (class "Default")
      (node (ref "R47") (pin "1") (pinfunction "1_1") (pintype "passive"))
      (node (ref "U10") (pin "51") (pinfunction "PC10_51") (pintype "bidirectional"))
      (node (ref "U6") (pin "4") (pinfunction "DI_4") (pintype "passive"))
    )
    (net (code "21") (name "/MCU_TX_5") (class "Default")
      (node (ref "R45") (pin "1") (pinfunction "1_1") (pintype "passive"))
      (node (ref "U10") (pin "53") (pinfunction "PC12_53") (pintype "bidirectional"))
      (node (ref "U5") (pin "4") (pinfunction "DI_4") (pintype "passive"))
    )
    (net (code "22") (name "/MLX_EN") (class "Default")
      (node (ref "R1") (pin "2") (pinfunction "2_2") (pintype "passive"))
      (node (ref "U1") (pin "3") (pinfunction "EN_3") (pintype "input"))
      (node (ref "U10") (pin "8") (pinfunction "PC0_8") (pintype "bidirectional"))
    )
    (net (code "23") (name "/NRST") (class "Default")
      (node (ref "H6") (pin "2") (pinfunction "2_2") (pintype "passive"))
      (node (ref "H7") (pin "2") (pinfunction "2_2") (pintype "passive"))
      (node (ref "R27") (pin "2") (pinfunction "2_2") (pintype "passive"))
      (node (ref "U10") (pin "7") (pinfunction "NRST_7") (pintype "bidirectional"))
    )
    (net (code "24") (name "/OPTO_EN") (class "Default")
      (node (ref "H2") (pin "2") (pinfunction "2_2") (pintype "passive"))
      (node (ref "U11") (pin "7") (pinfunction "7_7") (pintype "passive"))
    )
    (net (code "25") (name "/OSC_IN") (class "Default")
      (node (ref "C16") (pin "2") (pinfunction "2_2") (pintype "passive"))
      (node (ref "U10") (pin "5") (pinfunction "OSC_IN/PD0_5") (pintype "input"))
      (node (ref "Y1") (pin "1") (pinfunction "OSC1_1") (pintype "passive"))
    )
    (net (code "26") (name "/OSC_OUT") (class "Default")
      (node (ref "C22") (pin "2") (pinfunction "2_2") (pintype "passive"))
      (node (ref "U10") (pin "6") (pinfunction "OSC_OUT/PD1_6") (pintype "output"))
      (node (ref "Y1") (pin "2") (pinfunction "OSC2_2") (pintype "passive"))
    )
    (net (code "27") (name "/PPS") (class "Default")
      (node (ref "P4") (pin "5") (pinfunction "5_5") (pintype "passive"))
      (node (ref "U10") (pin "41") (pinfunction "PA8_41") (pintype "bidirectional"))
    )
    (net (code "28") (name "/RS485_1_N") (class "Default")
      (node (ref "R12") (pin "2") (pinfunction "2_2") (pintype "passive"))
      (node (ref "R15") (pin "1") (pinfunction "1_1") (pintype "passive"))
      (node (ref "R18") (pin "2") (pinfunction "2_2") (pintype "passive"))
      (node (ref "R43") (pin "2") (pinfunction "2_2") (pintype "passive"))
      (node (ref "U4") (pin "7") (pinfunction "B_7") (pintype "passive"))
    )
    (net (code "29") (name "/RS485_1_P") (class "Default")
      (node (ref "R12") (pin "1") (pinfunction "1_1") (pintype "passive"))
      (node (ref "R42") (pin "2") (pinfunction "2_2") (pintype "passive"))
      (node (ref "R6") (pin "1") (pinfunction "1_1") (pintype "passive"))
      (node (ref "R9") (pin "1") (pinfunction "1_1") (pintype "passive"))
      (node (ref "U4") (pin "6") (pinfunction "A_6") (pintype "passive"))
    )
    (net (code "30") (name "/RS485_4_N") (class "Default")
      (node (ref "R14") (pin "2") (pinfunction "2_2") (pintype "passive"))
      (node (ref "R17") (pin "1") (pinfunction "1_1") (pintype "passive"))
      (node (ref "R20") (pin "2") (pinfunction "2_2") (pintype "passive"))
      (node (ref "R46") (pin "2") (pinfunction "2_2") (pintype "passive"))
      (node (ref "U6") (pin "7") (pinfunction "B_7") (pintype "passive"))
    )
    (net (code "31") (name "/RS485_4_P") (class "Default")
      (node (ref "R11") (pin "1") (pinfunction "1_1") (pintype "passive"))
      (node (ref "R14") (pin "1") (pinfunction "1_1") (pintype "passive"))
      (node (ref "R47") (pin "2") (pinfunction "2_2") (pintype "passive"))
      (node (ref "R8") (pin "1") (pinfunction "1_1") (pintype "passive"))
      (node (ref "U6") (pin "6") (pinfunction "A_6") (pintype "passive"))
    )
    (net (code "32") (name "/RS485_5_N") (class "Default")
      (node (ref "R13") (pin "2") (pinfunction "2_2") (pintype "passive"))
      (node (ref "R16") (pin "1") (pinfunction "1_1") (pintype "passive"))
      (node (ref "R19") (pin "2") (pinfunction "2_2") (pintype "passive"))
      (node (ref "R44") (pin "2") (pinfunction "2_2") (pintype "passive"))
      (node (ref "U5") (pin "7") (pinfunction "B_7") (pintype "passive"))
    )
    (net (code "33") (name "/RS485_5_P") (class "Default")
      (node (ref "R10") (pin "1") (pinfunction "1_1") (pintype "passive"))
      (node (ref "R13") (pin "1") (pinfunction "1_1") (pintype "passive"))
      (node (ref "R45") (pin "2") (pinfunction "2_2") (pintype "passive"))
      (node (ref "R7") (pin "1") (pinfunction "1_1") (pintype "passive"))
      (node (ref "U5") (pin "6") (pinfunction "A_6") (pintype "passive"))
    )
    (net (code "34") (name "/RTS_1") (class "Default")
      (node (ref "U10") (pin "44") (pinfunction "PA11_44") (pintype "bidirectional"))
      (node (ref "U4") (pin "2") (pinfunction "/RE_2") (pintype "passive"))
      (node (ref "U4") (pin "3") (pinfunction "DE_3") (pintype "passive"))
    )
    (net (code "35") (name "/RTS_4") (class "Default")
      (node (ref "U10") (pin "50") (pinfunction "PA15/JTDI_50") (pintype "bidirectional"))
      (node (ref "U6") (pin "2") (pinfunction "/RE_2") (pintype "passive"))
      (node (ref "U6") (pin "3") (pinfunction "DE_3") (pintype "passive"))
    )
    (net (code "36") (name "/RTS_5") (class "Default")
      (node (ref "U10") (pin "56") (pinfunction "PB4/JNTRST_56") (pintype "bidirectional"))
      (node (ref "U5") (pin "2") (pinfunction "/RE_2") (pintype "passive"))
      (node (ref "U5") (pin "3") (pinfunction "DE_3") (pintype "passive"))
    )
    (net (code "37") (name "/SENDKEY") (class "Default")
      (node (ref "H8") (pin "6") (pinfunction "6_6") (pintype "passive"))
      (node (ref "R48") (pin "2") (pinfunction "2_2") (pintype "passive"))
      (node (ref "U10") (pin "24") (pinfunction "PC4_24") (pintype "bidirectional"))
    )
    (net (code "38") (name "/SPI1_MISO") (class "Default")
      (node (ref "H8") (pin "4") (pinfunction "4_4") (pintype "passive"))
      (node (ref "U10") (pin "22") (pinfunction "PA6_22") (pintype "bidirectional"))
    )
    (net (code "39") (name "/SPI1_MOSI") (class "Default")
      (node (ref "H8") (pin "5") (pinfunction "5_5") (pintype "passive"))
      (node (ref "U10") (pin "23") (pinfunction "PA7_23") (pintype "bidirectional"))
    )
    (net (code "40") (name "/SPI1_SCK") (class "Default")
      (node (ref "H8") (pin "3") (pinfunction "3_3") (pintype "passive"))
      (node (ref "U10") (pin "21") (pinfunction "PA5_21") (pintype "bidirectional"))
    )
    (net (code "41") (name "/SWCLK") (class "Default")
      (node (ref "H7") (pin "4") (pinfunction "4_4") (pintype "passive"))
      (node (ref "R37") (pin "2") (pinfunction "2_2") (pintype "passive"))
      (node (ref "U10") (pin "49") (pinfunction "PA14/JTCK/SWCLK_49") (pintype "bidirectional"))
    )
    (net (code "42") (name "/SWDIO") (class "Default")
      (node (ref "H7") (pin "5") (pinfunction "5_5") (pintype "passive"))
      (node (ref "R36") (pin "2") (pinfunction "2_2") (pintype "passive"))
      (node (ref "U10") (pin "46") (pinfunction "PA13/JTMS/SWDIO_46") (pintype "bidirectional"))
    )
    (net (code "43") (name "/SWO") (class "Default")
      (node (ref "H7") (pin "3") (pinfunction "3_3") (pintype "passive"))
      (node (ref "R41") (pin "2") (pinfunction "2_2") (pintype "passive"))
      (node (ref "U10") (pin "55") (pinfunction "PB3/JTDO_55") (pintype "bidirectional"))
    )
    (net (code "44") (name "3V3_BNO") (class "Default")
      (node (ref "C15") (pin "1") (pinfunction "1_1") (pintype "passive"))
      (node (ref "D5") (pin "1") (pinfunction "K_1") (pintype "passive"))
      (node (ref "P2") (pin "4") (pinfunction "4_4") (pintype "passive"))
      (node (ref "R2") (pin "2") (pinfunction "2_2") (pintype "passive"))
      (node (ref "R3") (pin "2") (pinfunction "2_2") (pintype "passive"))
      (node (ref "U8") (pin "5") (pinfunction "OUT_5") (pintype "power_in"))
    )
    (net (code "45") (name "3V3_ESP") (class "Default")
      (node (ref "C23") (pin "2") (pinfunction "2_2") (pintype "passive"))
      (node (ref "C24") (pin "2") (pinfunction "2_2") (pintype "passive"))
      (node (ref "C8") (pin "1") (pinfunction "1_1") (pintype "passive"))
      (node (ref "D3") (pin "1") (pinfunction "K_1") (pintype "passive"))
      (node (ref "R24") (pin "1") (pinfunction "1_1") (pintype "passive"))
      (node (ref "R25") (pin "2") (pinfunction "2_2") (pintype "passive"))
      (node (ref "R26") (pin "2") (pinfunction "2_2") (pintype "passive"))
      (node (ref "R28") (pin "2") (pinfunction "2_2") (pintype "passive"))
      (node (ref "R32") (pin "2") (pinfunction "2_2") (pintype "passive"))
      (node (ref "U11") (pin "8") (pinfunction "8_8") (pintype "passive"))
      (node (ref "U12") (pin "2") (pinfunction "2_2") (pintype "passive"))
      (node (ref "U3") (pin "5") (pinfunction "OUT_5") (pintype "power_in"))
      (node (ref "U9") (pin "8") (pinfunction "VCC_8") (pintype "passive"))
    )
    (net (code "46") (name "3V3_L80") (class "Default")
      (node (ref "C13") (pin "1") (pinfunction "1_1") (pintype "passive"))
      (node (ref "C9") (pin "2") (pinfunction "2_2") (pintype "passive"))
      (node (ref "D4") (pin "1") (pinfunction "K_1") (pintype "passive"))
      (node (ref "P4") (pin "4") (pinfunction "4_4") (pintype "passive"))
      (node (ref "R6") (pin "2") (pinfunction "2_2") (pintype "passive"))
      (node (ref "U4") (pin "8") (pinfunction "VCC_8") (pintype "passive"))
      (node (ref "U7") (pin "5") (pinfunction "OUT_5") (pintype "power_in"))
    )
    (net (code "47") (name "3V3_MCU") (class "Default")
      (node (ref "C10") (pin "2") (pinfunction "2_2") (pintype "passive"))
      (node (ref "C11") (pin "2") (pinfunction "2_2") (pintype "passive"))
      (node (ref "C17") (pin "2") (pinfunction "2_2") (pintype "passive"))
      (node (ref "C18") (pin "2") (pinfunction "2_2") (pintype "passive"))
      (node (ref "C19") (pin "2") (pinfunction "2_2") (pintype "passive"))
      (node (ref "C20") (pin "2") (pinfunction "2_2") (pintype "passive"))
      (node (ref "C21") (pin "2") (pinfunction "2_2") (pintype "passive"))
      (node (ref "C25") (pin "2") (pinfunction "2_2") (pintype "passive"))
      (node (ref "C28") (pin "2") (pinfunction "2_2") (pintype "passive"))
      (node (ref "C6") (pin "1") (pinfunction "1_1") (pintype "passive"))
      (node (ref "D2") (pin "1") (pinfunction "K_1") (pintype "passive"))
      (node (ref "H4") (pin "2") (pinfunction "2_2") (pintype "passive"))
      (node (ref "H7") (pin "6") (pinfunction "6_6") (pintype "passive"))
      (node (ref "R27") (pin "1") (pinfunction "1_1") (pintype "passive"))
      (node (ref "R33") (pin "1") (pinfunction "1_1") (pintype "passive"))
      (node (ref "R36") (pin "1") (pinfunction "1_1") (pintype "passive"))
      (node (ref "R37") (pin "1") (pinfunction "1_1") (pintype "passive"))
      (node (ref "R41") (pin "1") (pinfunction "1_1") (pintype "passive"))
      (node (ref "R48") (pin "1") (pinfunction "1_1") (pintype "passive"))
      (node (ref "R49") (pin "1") (pinfunction "1_1") (pintype "passive"))
      (node (ref "R7") (pin "2") (pinfunction "2_2") (pintype "passive"))
      (node (ref "R8") (pin "2") (pinfunction "2_2") (pintype "passive"))
      (node (ref "U10") (pin "1") (pinfunction "VBAT_1") (pintype "power_in"))
      (node (ref "U10") (pin "13") (pinfunction "VDDA_13") (pintype "power_in"))
      (node (ref "U10") (pin "19") (pinfunction "VDD_4_19") (pintype "power_in"))
      (node (ref "U10") (pin "32") (pinfunction "VDD_1_32") (pintype "power_in"))
      (node (ref "U10") (pin "48") (pinfunction "VDD_2_48") (pintype "power_in"))
      (node (ref "U10") (pin "64") (pinfunction "VDD_3_64") (pintype "power_in"))
      (node (ref "U11") (pin "2") (pinfunction "2_2") (pintype "passive"))
      (node (ref "U12") (pin "8") (pinfunction "8_8") (pintype "passive"))
      (node (ref "U2") (pin "5") (pinfunction "OUT_5") (pintype "power_in"))
      (node (ref "U5") (pin "8") (pinfunction "VCC_8") (pintype "passive"))
      (node (ref "U6") (pin "8") (pinfunction "VCC_8") (pintype "passive"))
    )
    (net (code "48") (name "3V3_MLX") (class "Default")
      (node (ref "C4") (pin "1") (pinfunction "1_1") (pintype "passive"))
      (node (ref "D1") (pin "1") (pinfunction "K_1") (pintype "passive"))
      (node (ref "P3") (pin "3") (pinfunction "3_3") (pintype "passive"))
      (node (ref "R4") (pin "2") (pinfunction "2_2") (pintype "passive"))
      (node (ref "R5") (pin "2") (pinfunction "2_2") (pintype "passive"))
      (node (ref "U1") (pin "5") (pinfunction "OUT_5") (pintype "power_in"))
    )
    (net (code "49") (name "ESP_BAT") (class "Default")
      (node (ref "C29") (pin "1") (pinfunction "1_1") (pintype "passive"))
      (node (ref "H1") (pin "2") (pinfunction "2_2") (pintype "passive"))
      (node (ref "R21") (pin "1") (pinfunction "1_1") (pintype "passive"))
      (node (ref "U3") (pin "1") (pinfunction "IN_1") (pintype "power_in"))
    )
    (net (code "50") (name "GND") (class "Default")
      (node (ref "C1") (pin "1") (pinfunction "1_1") (pintype "passive"))
      (node (ref "C30") (pin "2") (pinfunction "2_2") (pintype "passive"))
      (node (ref "F2") (pin "1") (pinfunction "1_1") (pintype "passive"))
      (node (ref "H1") (pin "4") (pinfunction "4_4") (pintype "passive"))
      (node (ref "P5") (pin "5") (pinfunction "5_5") (pintype "passive"))
      (node (ref "P6") (pin "5") (pinfunction "5_5") (pintype "passive"))
      (node (ref "P7") (pin "5") (pinfunction "5_5") (pintype "passive"))
      (node (ref "P8") (pin "5") (pinfunction "5_5") (pintype "passive"))
    )
    (net (code "51") (name "GNDD") (class "Default")
      (node (ref "C10") (pin "1") (pinfunction "1_1") (pintype "passive"))
      (node (ref "C11") (pin "1") (pinfunction "1_1") (pintype "passive"))
      (node (ref "C12") (pin "1") (pinfunction "1_1") (pintype "passive"))
      (node (ref "C13") (pin "2") (pinfunction "2_2") (pintype "passive"))
      (node (ref "C14") (pin "1") (pinfunction "1_1") (pintype "passive"))
      (node (ref "C15") (pin "2") (pinfunction "2_2") (pintype "passive"))
      (node (ref "C16") (pin "1") (pinfunction "1_1") (pintype "passive"))
      (node (ref "C17") (pin "1") (pinfunction "1_1") (pintype "passive"))
      (node (ref "C18") (pin "1") (pinfunction "1_1") (pintype "passive"))
      (node (ref "C19") (pin "1") (pinfunction "1_1") (pintype "passive"))
      (node (ref "C2") (pin "1") (pinfunction "1_1") (pintype "passive"))
      (node (ref "C20") (pin "1") (pinfunction "1_1") (pintype "passive"))
      (node (ref "C21") (pin "1") (pinfunction "1_1") (pintype "passive"))
      (node (ref "C22") (pin "1") (pinfunction "1_1") (pintype "passive"))
      (node (ref "C25") (pin "1") (pinfunction "1_1") (pintype "passive"))
      (node (ref "C26") (pin "1") (pinfunction "1_1") (pintype "passive"))
      (node (ref "C27") (pin "1") (pinfunction "1_1") (pintype "passive"))
      (node (ref "C28") (pin "1") (pinfunction "1_1") (pintype "passive"))
      (node (ref "C3") (pin "1") (pinfunction "1_1") (pintype "passive"))
      (node (ref "C4") (pin "2") (pinfunction "2_2") (pintype "passive"))
      (node (ref "C5") (pin "1") (pinfunction "1_1") (pintype "passive"))
      (node (ref "C6") (pin "2") (pinfunction "2_2") (pintype "passive"))
      (node (ref "C9") (pin "1") (pinfunction "1_1") (pintype "passive"))
      (node (ref "D1") (pin "2") (pinfunction "A_2") (pintype "passive"))
      (node (ref "D2") (pin "2") (pinfunction "A_2") (pintype "passive"))
      (node (ref "D4") (pin "2") (pinfunction "A_2") (pintype "passive"))
      (node (ref "D5") (pin "2") (pinfunction "A_2") (pintype "passive"))
      (node (ref "F2") (pin "2") (pinfunction "2_2") (pintype "passive"))
      (node (ref "H6") (pin "1") (pinfunction "1_1") (pintype "passive"))
      (node (ref "H7") (pin "1") (pinfunction "1_1") (pintype "passive"))
      (node (ref "H8") (pin "1") (pinfunction "1_1") (pintype "passive"))
      (node (ref "P2") (pin "5") (pinfunction "5_5") (pintype "passive"))
      (node (ref "P3") (pin "4") (pinfunction "4_4") (pintype "passive"))
      (node (ref "P4") (pin "3") (pinfunction "3_3") (pintype "passive"))
      (node (ref "P5") (pin "3") (pinfunction "3_3") (pintype "passive"))
      (node (ref "P6") (pin "3") (pinfunction "3_3") (pintype "passive"))
      (node (ref "P7") (pin "3") (pinfunction "3_3") (pintype "passive"))
      (node (ref "P8") (pin "3") (pinfunction "3_3") (pintype "passive"))
      (node (ref "R18") (pin "1") (pinfunction "1_1") (pintype "passive"))
      (node (ref "R19") (pin "1") (pinfunction "1_1") (pintype "passive"))
      (node (ref "R20") (pin "1") (pinfunction "1_1") (pintype "passive"))
      (node (ref "R29") (pin "2") (pinfunction "2_2") (pintype "passive"))
      (node (ref "R31") (pin "2") (pinfunction "2_2") (pintype "passive"))
      (node (ref "R38") (pin "1") (pinfunction "1_1") (pintype "passive"))
      (node (ref "U1") (pin "2") (pinfunction "GND_2") (pintype "power_in"))
      (node (ref "U10") (pin "12") (pinfunction "VSSA_12") (pintype "power_in"))
      (node (ref "U10") (pin "18") (pinfunction "VSS_4_18") (pintype "power_in"))
      (node (ref "U10") (pin "31") (pinfunction "VSS_1_31") (pintype "power_in"))
      (node (ref "U10") (pin "47") (pinfunction "VSS_2_47") (pintype "power_in"))
      (node (ref "U10") (pin "63") (pinfunction "VSS_3_63") (pintype "power_in"))
      (node (ref "U12") (pin "5") (pinfunction "GND_5") (pintype "passive"))
      (node (ref "U2") (pin "2") (pinfunction "GND_2") (pintype "power_in"))
      (node (ref "U4") (pin "5") (pinfunction "GND_5") (pintype "passive"))
      (node (ref "U5") (pin "5") (pinfunction "GND_5") (pintype "passive"))
      (node (ref "U6") (pin "5") (pinfunction "GND_5") (pintype "passive"))
      (node (ref "U7") (pin "2") (pinfunction "GND_2") (pintype "power_in"))
      (node (ref "U8") (pin "2") (pinfunction "GND_2") (pintype "power_in"))
    )
    (net (code "52") (name "GND_ESP") (class "Default")
      (node (ref "C23") (pin "1") (pinfunction "1_1") (pintype "passive"))
      (node (ref "C24") (pin "1") (pinfunction "1_1") (pintype "passive"))
      (node (ref "C29") (pin "2") (pinfunction "2_2") (pintype "passive"))
      (node (ref "C7") (pin "1") (pinfunction "1_1") (pintype "passive"))
      (node (ref "C8") (pin "2") (pinfunction "2_2") (pintype "passive"))
      (node (ref "D3") (pin "2") (pinfunction "A_2") (pintype "passive"))
      (node (ref "H1") (pin "1") (pinfunction "1_1") (pintype "passive"))
      (node (ref "H2") (pin "1") (pinfunction "1_1") (pintype "passive"))
      (node (ref "H3") (pin "1") (pinfunction "1_1") (pintype "passive"))
      (node (ref "H5") (pin "1") (pinfunction "1_1") (pintype "passive"))
      (node (ref "R30") (pin "2") (pinfunction "2_2") (pintype "passive"))
      (node (ref "R38") (pin "2") (pinfunction "2_2") (pintype "passive"))
      (node (ref "U11") (pin "5") (pinfunction "GND_5") (pintype "passive"))
      (node (ref "U3") (pin "2") (pinfunction "GND_2") (pintype "power_in"))
      (node (ref "U9") (pin "15") (pinfunction "GND_15") (pintype "passive"))
    )
    (net (code "53") (name "Net-(P4-Pad1)") (class "Default")
      (node (ref "P4") (pin "1") (pinfunction "1_1") (pintype "passive"))
      (node (ref "R15") (pin "2") (pinfunction "2_2") (pintype "passive"))
    )
    (net (code "54") (name "Net-(P4-Pad2)") (class "Default")
      (node (ref "P4") (pin "2") (pinfunction "2_2") (pintype "passive"))
      (node (ref "R9") (pin "2") (pinfunction "2_2") (pintype "passive"))
    )
    (net (code "55") (name "Net-(P5-Pad1)") (class "Default")
      (node (ref "P5") (pin "1") (pinfunction "1_1") (pintype "passive"))
      (node (ref "P8") (pin "1") (pinfunction "1_1") (pintype "passive"))
      (node (ref "R16") (pin "2") (pinfunction "2_2") (pintype "passive"))
    )
    (net (code "56") (name "Net-(P5-Pad2)") (class "Default")
      (node (ref "P5") (pin "2") (pinfunction "2_2") (pintype "passive"))
      (node (ref "P8") (pin "2") (pinfunction "2_2") (pintype "passive"))
      (node (ref "R10") (pin "2") (pinfunction "2_2") (pintype "passive"))
    )
    (net (code "57") (name "Net-(P6-Pad1)") (class "Default")
      (node (ref "P6") (pin "1") (pinfunction "1_1") (pintype "passive"))
      (node (ref "P7") (pin "1") (pinfunction "1_1") (pintype "passive"))
      (node (ref "R17") (pin "2") (pinfunction "2_2") (pintype "passive"))
    )
    (net (code "58") (name "Net-(P6-Pad2)") (class "Default")
      (node (ref "P6") (pin "2") (pinfunction "2_2") (pintype "passive"))
      (node (ref "P7") (pin "2") (pinfunction "2_2") (pintype "passive"))
      (node (ref "R11") (pin "2") (pinfunction "2_2") (pintype "passive"))
    )
    (net (code "59") (name "Net-(R34-Pad2)") (class "Default")
      (node (ref "R34") (pin "2") (pinfunction "2_2") (pintype "passive"))
      (node (ref "U11") (pin "3") (pinfunction "3_3") (pintype "passive"))
    )
    (net (code "60") (name "Net-(R35-Pad1)") (class "Default")
      (node (ref "R35") (pin "1") (pinfunction "1_1") (pintype "passive"))
      (node (ref "U12") (pin "3") (pinfunction "3_3") (pintype "passive"))
    )
    (net (code "61") (name "Net-(U1-BYP)") (class "Default")
      (node (ref "C3") (pin "2") (pinfunction "2_2") (pintype "passive"))
      (node (ref "U1") (pin "4") (pinfunction "BYP_4") (pintype "bidirectional"))
    )
    (net (code "62") (name "Net-(U2-BYP)") (class "Default")
      (node (ref "C5") (pin "2") (pinfunction "2_2") (pintype "passive"))
      (node (ref "U2") (pin "4") (pinfunction "BYP_4") (pintype "bidirectional"))
    )
    (net (code "63") (name "Net-(U3-BYP)") (class "Default")
      (node (ref "C7") (pin "2") (pinfunction "2_2") (pintype "passive"))
      (node (ref "U3") (pin "4") (pinfunction "BYP_4") (pintype "bidirectional"))
    )
    (net (code "64") (name "Net-(U7-BYP)") (class "Default")
      (node (ref "C12") (pin "2") (pinfunction "2_2") (pintype "passive"))
      (node (ref "U7") (pin "4") (pinfunction "BYP_4") (pintype "bidirectional"))
    )
    (net (code "65") (name "Net-(U8-BYP)") (class "Default")
      (node (ref "C14") (pin "2") (pinfunction "2_2") (pintype "passive"))
      (node (ref "U8") (pin "4") (pinfunction "BYP_4") (pintype "bidirectional"))
    )
    (net (code "66") (name "Net-(U9-EN(CH-PD))") (class "Default")
      (node (ref "R25") (pin "1") (pinfunction "1_1") (pintype "passive"))
      (node (ref "U9") (pin "3") (pinfunction "EN(CH-PD)_3") (pintype "passive"))
    )
    (net (code "67") (name "Net-(U9-GPIO2)") (class "Default")
      (node (ref "R26") (pin "1") (pinfunction "1_1") (pintype "passive"))
      (node (ref "U9") (pin "17") (pinfunction "GPIO2_17") (pintype "passive"))
    )
    (net (code "68") (name "Net-(U9-GPIO15)") (class "Default")
      (node (ref "R30") (pin "1") (pinfunction "1_1") (pintype "passive"))
      (node (ref "U9") (pin "16") (pinfunction "GPIO15_16") (pintype "passive"))
    )
    (net (code "69") (name "Net-(U9-~{RST})") (class "Default")
      (node (ref "R24") (pin "2") (pinfunction "2_2") (pintype "passive"))
      (node (ref "U9") (pin "1") (pinfunction "~{RST}_1") (pintype "passive"))
    )
    (net (code "70") (name "Net-(U10-PB2{slash}BOOT1)") (class "Default")
      (node (ref "R29") (pin "1") (pinfunction "1_1") (pintype "passive"))
      (node (ref "U10") (pin "28") (pinfunction "PB2/BOOT1_28") (pintype "bidirectional"))
    )
    (net (code "71") (name "Net-(U10-PC14-OSC32_IN)") (class "Default")
      (node (ref "C27") (pin "2") (pinfunction "2_2") (pintype "passive"))
      (node (ref "U10") (pin "3") (pinfunction "PC14-OSC32_IN_3") (pintype "bidirectional"))
    )
    (net (code "72") (name "Net-(U10-PC15-OSC32_OUT)") (class "Default")
      (node (ref "C26") (pin "2") (pinfunction "2_2") (pintype "passive"))
      (node (ref "U10") (pin "4") (pinfunction "PC15-OSC32_OUT_4") (pintype "bidirectional"))
    )
    (net (code "73") (name "VCC_IN") (class "Default")
      (node (ref "C1") (pin "2") (pinfunction "2_2") (pintype "passive"))
      (node (ref "C30") (pin "1") (pinfunction "1_1") (pintype "passive"))
      (node (ref "F1") (pin "1") (pinfunction "1_1") (pintype "passive"))
      (node (ref "H1") (pin "3") (pinfunction "3_3") (pintype "passive"))
      (node (ref "P5") (pin "4") (pinfunction "4_4") (pintype "passive"))
      (node (ref "P6") (pin "4") (pinfunction "4_4") (pintype "passive"))
      (node (ref "P7") (pin "4") (pinfunction "4_4") (pintype "passive"))
      (node (ref "P8") (pin "4") (pinfunction "4_4") (pintype "passive"))
    )
    (net (code "74") (name "VCC_IN_D") (class "Default")
      (node (ref "C2") (pin "2") (pinfunction "2_2") (pintype "passive"))
      (node (ref "F1") (pin "2") (pinfunction "2_2") (pintype "passive"))
      (node (ref "R1") (pin "1") (pinfunction "1_1") (pintype "passive"))
      (node (ref "R22") (pin "1") (pinfunction "1_1") (pintype "passive"))
      (node (ref "R23") (pin "1") (pinfunction "1_1") (pintype "passive"))
      (node (ref "U1") (pin "1") (pinfunction "IN_1") (pintype "power_in"))
      (node (ref "U2") (pin "1") (pinfunction "IN_1") (pintype "power_in"))
      (node (ref "U2") (pin "3") (pinfunction "EN_3") (pintype "input"))
      (node (ref "U7") (pin "1") (pinfunction "IN_1") (pintype "power_in"))
      (node (ref "U8") (pin "1") (pinfunction "IN_1") (pintype "power_in"))
    )
    (net (code "75") (name "unconnected-(H3-Pad2)") (class "Default")
      (node (ref "H3") (pin "2") (pinfunction "2_2") (pintype "passive+no_connect"))
    )
    (net (code "76") (name "unconnected-(H3-Pad4)") (class "Default")
      (node (ref "H3") (pin "4") (pinfunction "4_4") (pintype "passive+no_connect"))
    )
    (net (code "77") (name "unconnected-(H3-Pad6)") (class "Default")
      (node (ref "H3") (pin "6") (pinfunction "6_6") (pintype "passive+no_connect"))
    )
    (net (code "78") (name "unconnected-(U9-ADC-Pad2)") (class "Default")
      (node (ref "U9") (pin "2") (pinfunction "ADC_2") (pintype "passive+no_connect"))
    )
    (net (code "79") (name "unconnected-(U9-CS0-Pad9)") (class "Default")
      (node (ref "U9") (pin "9") (pinfunction "CS0_9") (pintype "passive+no_connect"))
    )
    (net (code "80") (name "unconnected-(U9-GPIO4-Pad19)") (class "Default")
      (node (ref "U9") (pin "19") (pinfunction "GPIO4_19") (pintype "passive+no_connect"))
    )
    (net (code "81") (name "unconnected-(U9-GPIO5-Pad20)") (class "Default")
      (node (ref "U9") (pin "20") (pinfunction "GPIO5_20") (pintype "passive+no_connect"))
    )
    (net (code "82") (name "unconnected-(U9-GPIO9-Pad11)") (class "Default")
      (node (ref "U9") (pin "11") (pinfunction "GPIO9_11") (pintype "passive+no_connect"))
    )
    (net (code "83") (name "unconnected-(U9-GPIO10-Pad12)") (class "Default")
      (node (ref "U9") (pin "12") (pinfunction "GPIO10_12") (pintype "passive+no_connect"))
    )
    (net (code "84") (name "unconnected-(U9-GPIO12-Pad6)") (class "Default")
      (node (ref "U9") (pin "6") (pinfunction "GPIO12_6") (pintype "passive+no_connect"))
    )
    (net (code "85") (name "unconnected-(U9-GPIO13-Pad7)") (class "Default")
      (node (ref "U9") (pin "7") (pinfunction "GPIO13_7") (pintype "passive+no_connect"))
    )
    (net (code "86") (name "unconnected-(U9-GPIO14-Pad5)") (class "Default")
      (node (ref "U9") (pin "5") (pinfunction "GPIO14_5") (pintype "passive+no_connect"))
    )
    (net (code "87") (name "unconnected-(U9-GPIO16-Pad4)") (class "Default")
      (node (ref "U9") (pin "4") (pinfunction "GPIO16_4") (pintype "passive+no_connect"))
    )
    (net (code "88") (name "unconnected-(U9-MISO-Pad10)") (class "Default")
      (node (ref "U9") (pin "10") (pinfunction "MISO_10") (pintype "passive+no_connect"))
    )
    (net (code "89") (name "unconnected-(U9-MOSI-Pad13)") (class "Default")
      (node (ref "U9") (pin "13") (pinfunction "MOSI_13") (pintype "passive+no_connect"))
    )
    (net (code "90") (name "unconnected-(U9-SCLK-Pad14)") (class "Default")
      (node (ref "U9") (pin "14") (pinfunction "SCLK_14") (pintype "passive+no_connect"))
    )
    (net (code "91") (name "unconnected-(U10-PA0-WKUP-Pad14)") (class "Default")
      (node (ref "U10") (pin "14") (pinfunction "PA0-WKUP_14") (pintype "bidirectional"))
    )
    (net (code "92") (name "unconnected-(U10-PA1-Pad15)") (class "Default")
      (node (ref "U10") (pin "15") (pinfunction "PA1_15") (pintype "bidirectional"))
    )
    (net (code "93") (name "unconnected-(U10-PA12-Pad45)") (class "Default")
      (node (ref "U10") (pin "45") (pinfunction "PA12_45") (pintype "bidirectional"))
    )
    (net (code "94") (name "unconnected-(U10-PB0-Pad26)") (class "Default")
      (node (ref "U10") (pin "26") (pinfunction "PB0_26") (pintype "bidirectional"))
    )
    (net (code "95") (name "unconnected-(U10-PB1-Pad27)") (class "Default")
      (node (ref "U10") (pin "27") (pinfunction "PB1_27") (pintype "bidirectional"))
    )
    (net (code "96") (name "unconnected-(U10-PB5-Pad57)") (class "Default")
      (node (ref "U10") (pin "57") (pinfunction "PB5_57") (pintype "bidirectional"))
    )
    (net (code "97") (name "unconnected-(U10-PB8-Pad61)") (class "Default")
      (node (ref "U10") (pin "61") (pinfunction "PB8_61") (pintype "bidirectional"))
    )
    (net (code "98") (name "unconnected-(U10-PB9-Pad62)") (class "Default")
      (node (ref "U10") (pin "62") (pinfunction "PB9_62") (pintype "bidirectional"))
    )
    (net (code "99") (name "unconnected-(U10-PB13-Pad34)") (class "Default")
      (node (ref "U10") (pin "34") (pinfunction "PB13_34") (pintype "bidirectional"))
    )
    (net (code "100") (name "unconnected-(U10-PB14-Pad35)") (class "Default")
      (node (ref "U10") (pin "35") (pinfunction "PB14_35") (pintype "bidirectional"))
    )
    (net (code "101") (name "unconnected-(U10-PB15-Pad36)") (class "Default")
      (node (ref "U10") (pin "36") (pinfunction "PB15_36") (pintype "bidirectional"))
    )
    (net (code "102") (name "unconnected-(U10-PC5-Pad25)") (class "Default")
      (node (ref "U10") (pin "25") (pinfunction "PC5_25") (pintype "bidirectional"))
    )
    (net (code "103") (name "unconnected-(U10-PC6-Pad37)") (class "Default")
      (node (ref "U10") (pin "37") (pinfunction "PC6_37") (pintype "bidirectional"))
    )
    (net (code "104") (name "unconnected-(U10-PC7-Pad38)") (class "Default")
      (node (ref "U10") (pin "38") (pinfunction "PC7_38") (pintype "bidirectional"))
    )
    (net (code "105") (name "unconnected-(U10-PC8-Pad39)") (class "Default")
      (node (ref "U10") (pin "39") (pinfunction "PC8_39") (pintype "bidirectional"))
    )
    (net (code "106") (name "unconnected-(U10-PC9-Pad40)") (class "Default")
      (node (ref "U10") (pin "40") (pinfunction "PC9_40") (pintype "bidirectional"))
    )
    (net (code "107") (name "unconnected-(U10-PC13-TAMPER-RTC-Pad2)") (class "Default")
      (node (ref "U10") (pin "2") (pinfunction "PC13-TAMPER-RTC_2") (pintype "bidirectional"))
    )
    (net (code "108") (name "unconnected-(U11-Pad1)") (class "Default")
      (node (ref "U11") (pin "1") (pinfunction "1_1") (pintype "passive+no_connect"))
    )
    (net (code "109") (name "unconnected-(U11-Pad4)") (class "Default")
      (node (ref "U11") (pin "4") (pinfunction "4_4") (pintype "passive+no_connect"))
    )
    (net (code "110") (name "unconnected-(U12-Pad1)") (class "Default")
      (node (ref "U12") (pin "1") (pinfunction "1_1") (pintype "passive+no_connect"))
    )
    (net (code "111") (name "unconnected-(U12-Pad4)") (class "Default")
      (node (ref "U12") (pin "4") (pinfunction "4_4") (pintype "passive+no_connect"))
    )
    (net (code "112") (name "unconnected-(U12-Pad7)") (class "Default")
      (node (ref "U12") (pin "7") (pinfunction "7_7") (pintype "passive+no_connect"))
    )
  )
)
